# MOSFET_V2.net
KiCad netlist of a schematic drawn in Altium Designer
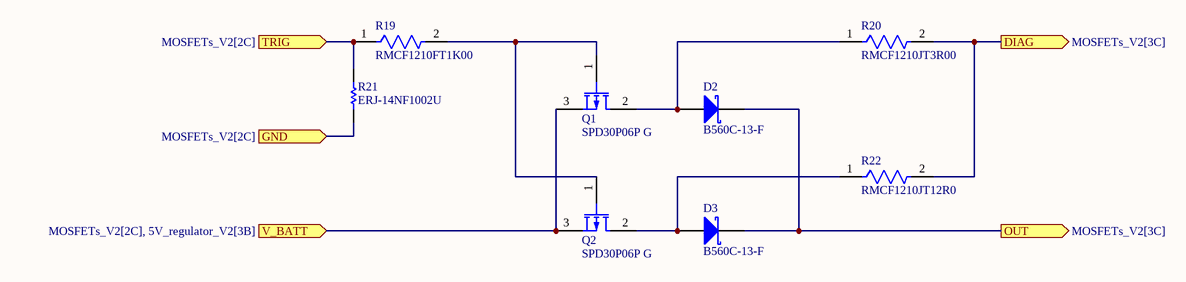
[diagram p0: MOSFET_V2.SchDoc]

(export (version "E")
  (design (tool "Eeschema 10.0.6"))
  (components
    (comp (ref "D2")
      (value "B560C-13-F")
      (footprint "DIOD-B5X0C-2_M")
      (description "Schottky Barrier Rectifier, 5 A, 60 V, -55 to 125 degC, 2-Pin SMD, RoHS, Tape and Reel")
      (fields (field (name "MANUFACTURER") "DiodesIncorporated"))
      (libsource (lib "Altium Content Vault") (part "DSKY-KA-2"))
    )
    (comp (ref "D3")
      (value "B560C-13-F")
      (footprint "DIOD-B5X0C-2_M")
      (description "Schottky Barrier Rectifier, 5 A, 60 V, -55 to 125 degC, 2-Pin SMD, RoHS, Tape and Reel")
      (fields (field (name "MANUFACTURER") "DiodesIncorporated"))
      (libsource (lib "Altium Content Vault") (part "DSKY-KA-2"))
    )
    (comp (ref "Q1")
      (value "SPD30P06P G")
      (footprint "INF-PG-TO252-3-1_N")
      (description "P-Channel SIPMOS Power-Transistor, -60 V VDS, -30 A ID, -55 to 175 degC, PG-TO252-3-1, Reel, Green")
      (fields (field (name "MANUFACTURER") "Infineon"))
      (libsource (lib "Altium Content Vault") (part "INF-SPD30P06PG-PG-TO252-3-313-3"))
    )
    (comp (ref "Q2")
      (value "SPD30P06P G")
      (footprint "INF-PG-TO252-3-1_N")
      (description "P-Channel SIPMOS Power-Transistor, -60 V VDS, -30 A ID, -55 to 175 degC, PG-TO252-3-1, Reel, Green")
      (fields (field (name "MANUFACTURER") "Infineon"))
      (libsource (lib "Altium Content Vault") (part "INF-SPD30P06PG-PG-TO252-3-313-3"))
    )
    (comp (ref "R19")
      (value "RMCF1210FT1K00")
      (footprint "FP-RMCF1210-IPC_A")
      (description "1kΩ ±1% 0.5W 1210 Thick Film Chip Resistor AEC-Q200 compliant")
      (fields (field (name "TOLERANCE") "1%"))
      (libsource (lib "Altium Content Vault") (part "1029c3af85768c4190bb7ad29bc67b5"))
    )
    (comp (ref "R20")
      (value "RMCF1210JT3R00")
      (footprint "FP-RMCF1210-IPC_A")
      (description "3Ω ±5% 0.5W 1210 Thick Film Chip Resistor AEC-Q200 compliant")
      (fields (field (name "TOLERANCE") "5%"))
      (libsource (lib "Altium Content Vault") (part "1029c3af85768c4190bb7ad29bc67b5"))
    )
    (comp (ref "R21")
      (value "ERJ-14NF1002U")
      (footprint "RESC3225X70X50NL20T20")
      (fields (field (name "MANUFACTURER") "Panasonic"))
      (libsource (lib "Altium Content Vault") (part "RES"))
    )
    (comp (ref "R22")
      (value "RMCF1210JT12R0")
      (footprint "FP-RMCF1210-IPC_B")
      (description "12Ω ±5% 0.5W 1210 Thick Film Chip Resistor AEC-Q200 compliant")
      (fields (field (name "TOLERANCE") "5%"))
      (libsource (lib "Altium Content Vault") (part "1029c3af85768c4190bb7ad29bc67b5"))
    )
  )
  (nets
    (net (code "1") (name "/DIAG") (class "Default")
      (node (ref "R20") (pin "2") (pinfunction "2_2") (pintype "passive"))
      (node (ref "R22") (pin "2") (pinfunction "2_2") (pintype "passive"))
    )
    (net (code "2") (name "/GND") (class "Default")
      (node (ref "R21") (pin "2") (pinfunction "2_2") (pintype "passive"))
    )
    (net (code "3") (name "/OUT") (class "Default")
      (node (ref "D2") (pin "1") (pinfunction "K_1") (pintype "passive"))
      (node (ref "D3") (pin "1") (pinfunction "K_1") (pintype "passive"))
    )
    (net (code "4") (name "/TRIG") (class "Default")
      (node (ref "R19") (pin "1") (pinfunction "1_1") (pintype "passive"))
      (node (ref "R21") (pin "1") (pinfunction "1_1") (pintype "passive"))
    )
    (net (code "5") (name "/V_BATT") (class "Default")
      (node (ref "Q1") (pin "3") (pinfunction "S_3") (pintype "passive"))
      (node (ref "Q2") (pin "3") (pinfunction "S_3") (pintype "passive"))
    )
    (net (code "6") (name "Net-(D2-A)") (class "Default")
      (node (ref "D2") (pin "2") (pinfunction "A_2") (pintype "passive"))
      (node (ref "Q1") (pin "2") (pinfunction "D_2") (pintype "passive"))
      (node (ref "R20") (pin "1") (pinfunction "1_1") (pintype "passive"))
    )
    (net (code "7") (name "Net-(D3-A)") (class "Default")
      (node (ref "D3") (pin "2") (pinfunction "A_2") (pintype "passive"))
      (node (ref "Q2") (pin "2") (pinfunction "D_2") (pintype "passive"))
      (node (ref "R22") (pin "1") (pinfunction "1_1") (pintype "passive"))
    )
    (net (code "8") (name "Net-(Q1-G)") (class "Default")
      (node (ref "Q1") (pin "1") (pinfunction "G_1") (pintype "passive"))
      (node (ref "Q2") (pin "1") (pinfunction "G_1") (pintype "passive"))
      (node (ref "R19") (pin "2") (pinfunction "2_2") (pintype "passive"))
    )
  )
)
